# SPTSquidBoard.net
KiCad netlist of a schematic drawn in Altium Designer
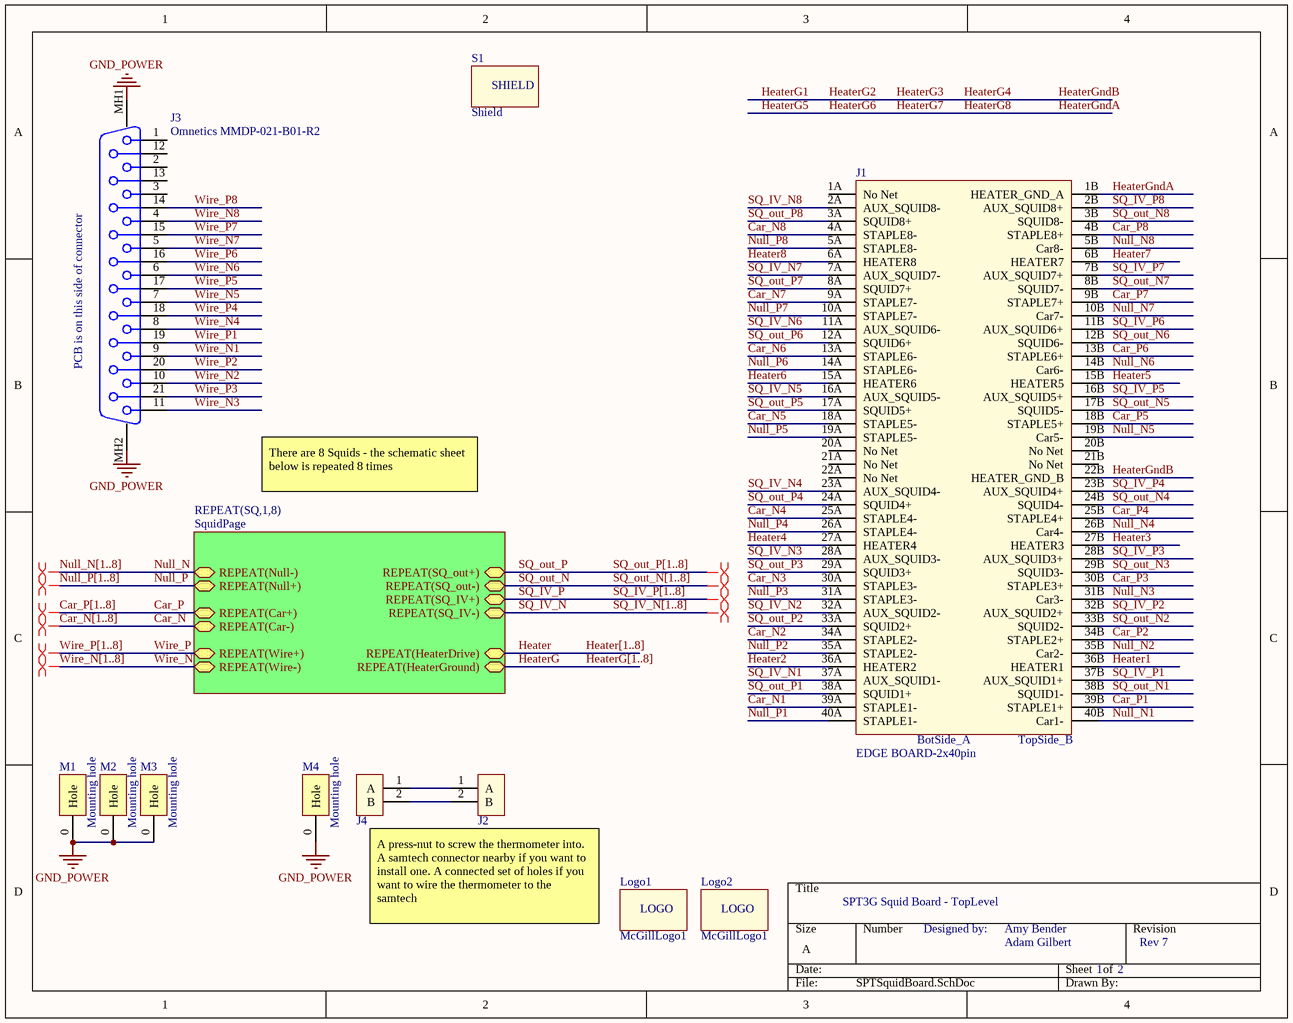
[diagram p0: SPTSquidBoard.SchDoc]

(export (version "E")
  (design (tool "Eeschema 10.0.6"))
  (components
    (comp (ref "J1")
      (value "EDGE BOARD-2x40pin")
      (description "Edge connector")
      (libsource (lib "SPT3G_LCBoard") (part "EDGE BOARD-2x40pin"))
    )
    (comp (ref "J2")
      (value "TempSenseWireConnection")
      (footprint "TempSenseWireCons")
      (libsource (lib "") (part "TempSenseCon_1"))
    )
    (comp (ref "J3")
      (value "Omnetics MMDP-021-B01-R2")
      (footprint "MMDP-021-B02-R2")
      (description "OmneticsMicroD21")
      (libsource (lib "SPT3G_LCBoard") (part "OmneticsMicroD21"))
    )
    (comp (ref "J4")
      (value "TempSenseWireConnection")
      (footprint "TempSenseWireCons")
      (libsource (lib "SPT3G_LCBoard") (part "TempSenseCon"))
    )
    (comp (ref "Logo1")
      (value "McGillLogo1")
      (footprint "McGillLogo1")
      (libsource (lib "SPT3G_LCBoard") (part "Logo"))
    )
    (comp (ref "Logo2")
      (value "McGillLogo1")
      (footprint "McGillLogo1")
      (libsource (lib "SPT3G_LCBoard") (part "Logo"))
    )
    (comp (ref "M1")
      (value "Mounting hole")
      (footprint "MountingHoleSquidBoard")
      (libsource (lib "SPT3G_LCBoard") (part "SquidBoardMountingHole"))
    )
    (comp (ref "M2")
      (value "Mounting hole")
      (footprint "MountingHoleSquidBoard")
      (libsource (lib "SPT3G_LCBoard") (part "SquidBoardMountingHole"))
    )
    (comp (ref "M3")
      (value "Mounting hole")
      (footprint "MountingHoleSquidBoard")
      (libsource (lib "SPT3G_LCBoard") (part "SquidBoardMountingHole"))
    )
    (comp (ref "M4")
      (value "Mounting hole")
      (footprint "MountingHoleSquidBoard")
      (libsource (lib "SPT3G_LCBoard") (part "SquidBoardMountingHole"))
    )
    (comp (ref "S1") (value "Shield") (footprint "Shield") (libsource (lib "SPT3G_LCBoard") (part "Shield")))
  )
  (nets
    (net (code "2") (name "/Car_N1") (class "Default")
      (node (ref "J1") (pin "39A") (pinfunction "STAPLE1-_39A") (pintype "passive"))
    )
    (net (code "3") (name "/Car_N2") (class "Default")
      (node (ref "J1") (pin "34A") (pinfunction "STAPLE2-_34A") (pintype "passive"))
    )
    (net (code "4") (name "/Car_N3") (class "Default")
      (node (ref "J1") (pin "30A") (pinfunction "STAPLE3-_30A") (pintype "passive"))
    )
    (net (code "5") (name "/Car_N4") (class "Default")
      (node (ref "J1") (pin "25A") (pinfunction "STAPLE4-_25A") (pintype "passive"))
    )
    (net (code "6") (name "/Car_N5") (class "Default")
      (node (ref "J1") (pin "18A") (pinfunction "STAPLE5-_18A") (pintype "passive"))
    )
    (net (code "7") (name "/Car_N6") (class "Default")
      (node (ref "J1") (pin "13A") (pinfunction "STAPLE6-_13A") (pintype "passive"))
    )
    (net (code "8") (name "/Car_N7") (class "Default")
      (node (ref "J1") (pin "9A") (pinfunction "STAPLE7-_9A") (pintype "passive"))
    )
    (net (code "9") (name "/Car_N8") (class "Default")
      (node (ref "J1") (pin "4A") (pinfunction "STAPLE8-_4A") (pintype "passive"))
    )
    (net (code "12") (name "/Car_P1") (class "Default")
      (node (ref "J1") (pin "39B") (pinfunction "STAPLE1+_39B") (pintype "passive"))
    )
    (net (code "13") (name "/Car_P2") (class "Default")
      (node (ref "J1") (pin "34B") (pinfunction "STAPLE2+_34B") (pintype "passive"))
    )
    (net (code "14") (name "/Car_P3") (class "Default")
      (node (ref "J1") (pin "30B") (pinfunction "STAPLE3+_30B") (pintype "passive"))
    )
    (net (code "15") (name "/Car_P4") (class "Default")
      (node (ref "J1") (pin "25B") (pinfunction "STAPLE4+_25B") (pintype "passive"))
    )
    (net (code "16") (name "/Car_P5") (class "Default")
      (node (ref "J1") (pin "18B") (pinfunction "STAPLE5+_18B") (pintype "passive"))
    )
    (net (code "17") (name "/Car_P6") (class "Default")
      (node (ref "J1") (pin "13B") (pinfunction "STAPLE6+_13B") (pintype "passive"))
    )
    (net (code "18") (name "/Car_P7") (class "Default")
      (node (ref "J1") (pin "9B") (pinfunction "STAPLE7+_9B") (pintype "passive"))
    )
    (net (code "19") (name "/Car_P8") (class "Default")
      (node (ref "J1") (pin "4B") (pinfunction "STAPLE8+_4B") (pintype "passive"))
    )
    (net (code "22") (name "/Heater1") (class "Default")
      (node (ref "J1") (pin "36B") (pinfunction "HEATER1_36B") (pintype "passive"))
    )
    (net (code "23") (name "/Heater2") (class "Default")
      (node (ref "J1") (pin "36A") (pinfunction "HEATER2_36A") (pintype "passive"))
    )
    (net (code "24") (name "/Heater3") (class "Default")
      (node (ref "J1") (pin "27B") (pinfunction "HEATER3_27B") (pintype "passive"))
    )
    (net (code "25") (name "/Heater4") (class "Default")
      (node (ref "J1") (pin "27A") (pinfunction "HEATER4_27A") (pintype "passive"))
    )
    (net (code "26") (name "/Heater5") (class "Default")
      (node (ref "J1") (pin "15B") (pinfunction "HEATER5_15B") (pintype "passive"))
    )
    (net (code "27") (name "/Heater6") (class "Default")
      (node (ref "J1") (pin "15A") (pinfunction "HEATER6_15A") (pintype "passive"))
    )
    (net (code "28") (name "/Heater7") (class "Default")
      (node (ref "J1") (pin "6B") (pinfunction "HEATER7_6B") (pintype "passive"))
    )
    (net (code "29") (name "/Heater8") (class "Default")
      (node (ref "J1") (pin "6A") (pinfunction "HEATER8_6A") (pintype "passive"))
    )
    (net (code "31") (name "/HeaterG4") (class "Default")
      (node (ref "J1") (pin "22B") (pinfunction "HEATER_GND_B_22B") (pintype "passive"))
    )
    (net (code "32") (name "/HeaterG8") (class "Default")
      (node (ref "J1") (pin "1B") (pinfunction "HEATER_GND_A_1B") (pintype "passive"))
    )
    (net (code "36") (name "/Null_N1") (class "Default")
      (node (ref "J1") (pin "40B") (pinfunction "Car1-_40B") (pintype "passive"))
    )
    (net (code "37") (name "/Null_N2") (class "Default")
      (node (ref "J1") (pin "35B") (pinfunction "Car2-_35B") (pintype "passive"))
    )
    (net (code "38") (name "/Null_N3") (class "Default")
      (node (ref "J1") (pin "31B") (pinfunction "Car3-_31B") (pintype "passive"))
    )
    (net (code "39") (name "/Null_N4") (class "Default")
      (node (ref "J1") (pin "26B") (pinfunction "Car4-_26B") (pintype "passive"))
    )
    (net (code "40") (name "/Null_N5") (class "Default")
      (node (ref "J1") (pin "19B") (pinfunction "Car5-_19B") (pintype "passive"))
    )
    (net (code "41") (name "/Null_N6") (class "Default")
      (node (ref "J1") (pin "14B") (pinfunction "Car6-_14B") (pintype "passive"))
    )
    (net (code "42") (name "/Null_N7") (class "Default")
      (node (ref "J1") (pin "10B") (pinfunction "Car7-_10B") (pintype "passive"))
    )
    (net (code "43") (name "/Null_N8") (class "Default")
      (node (ref "J1") (pin "5B") (pinfunction "Car8-_5B") (pintype "passive"))
    )
    (net (code "46") (name "/Null_P1") (class "Default")
      (node (ref "J1") (pin "40A") (pinfunction "STAPLE1-_40A") (pintype "passive"))
    )
    (net (code "47") (name "/Null_P2") (class "Default")
      (node (ref "J1") (pin "35A") (pinfunction "STAPLE2-_35A") (pintype "passive"))
    )
    (net (code "48") (name "/Null_P3") (class "Default")
      (node (ref "J1") (pin "31A") (pinfunction "STAPLE3-_31A") (pintype "passive"))
    )
    (net (code "49") (name "/Null_P4") (class "Default")
      (node (ref "J1") (pin "26A") (pinfunction "STAPLE4-_26A") (pintype "passive"))
    )
    (net (code "50") (name "/Null_P5") (class "Default")
      (node (ref "J1") (pin "19A") (pinfunction "STAPLE5-_19A") (pintype "passive"))
    )
    (net (code "51") (name "/Null_P6") (class "Default")
      (node (ref "J1") (pin "14A") (pinfunction "STAPLE6-_14A") (pintype "passive"))
    )
    (net (code "52") (name "/Null_P7") (class "Default")
      (node (ref "J1") (pin "10A") (pinfunction "STAPLE7-_10A") (pintype "passive"))
    )
    (net (code "53") (name "/Null_P8") (class "Default")
      (node (ref "J1") (pin "5A") (pinfunction "STAPLE8-_5A") (pintype "passive"))
    )
    (net (code "56") (name "/SQ_IV_N1") (class "Default")
      (node (ref "J1") (pin "37A") (pinfunction "AUX_SQUID1-_37A") (pintype "passive"))
    )
    (net (code "57") (name "/SQ_IV_N2") (class "Default")
      (node (ref "J1") (pin "32A") (pinfunction "AUX_SQUID2-_32A") (pintype "passive"))
    )
    (net (code "58") (name "/SQ_IV_N3") (class "Default")
      (node (ref "J1") (pin "28A") (pinfunction "AUX_SQUID3-_28A") (pintype "passive"))
    )
    (net (code "59") (name "/SQ_IV_N4") (class "Default")
      (node (ref "J1") (pin "23A") (pinfunction "AUX_SQUID4-_23A") (pintype "passive"))
    )
    (net (code "60") (name "/SQ_IV_N5") (class "Default")
      (node (ref "J1") (pin "16A") (pinfunction "AUX_SQUID5-_16A") (pintype "passive"))
    )
    (net (code "61") (name "/SQ_IV_N6") (class "Default")
      (node (ref "J1") (pin "11A") (pinfunction "AUX_SQUID6-_11A") (pintype "passive"))
    )
    (net (code "62") (name "/SQ_IV_N7") (class "Default")
      (node (ref "J1") (pin "7A") (pinfunction "AUX_SQUID7-_7A") (pintype "passive"))
    )
    (net (code "63") (name "/SQ_IV_N8") (class "Default")
      (node (ref "J1") (pin "2A") (pinfunction "AUX_SQUID8-_2A") (pintype "passive"))
    )
    (net (code "66") (name "/SQ_IV_P1") (class "Default")
      (node (ref "J1") (pin "37B") (pinfunction "AUX_SQUID1+_37B") (pintype "passive"))
    )
    (net (code "67") (name "/SQ_IV_P2") (class "Default")
      (node (ref "J1") (pin "32B") (pinfunction "AUX_SQUID2+_32B") (pintype "passive"))
    )
    (net (code "68") (name "/SQ_IV_P3") (class "Default")
      (node (ref "J1") (pin "28B") (pinfunction "AUX_SQUID3+_28B") (pintype "passive"))
    )
    (net (code "69") (name "/SQ_IV_P4") (class "Default")
      (node (ref "J1") (pin "23B") (pinfunction "AUX_SQUID4+_23B") (pintype "passive"))
    )
    (net (code "70") (name "/SQ_IV_P5") (class "Default")
      (node (ref "J1") (pin "16B") (pinfunction "AUX_SQUID5+_16B") (pintype "passive"))
    )
    (net (code "71") (name "/SQ_IV_P6") (class "Default")
      (node (ref "J1") (pin "11B") (pinfunction "AUX_SQUID6+_11B") (pintype "passive"))
    )
    (net (code "72") (name "/SQ_IV_P7") (class "Default")
      (node (ref "J1") (pin "7B") (pinfunction "AUX_SQUID7+_7B") (pintype "passive"))
    )
    (net (code "73") (name "/SQ_IV_P8") (class "Default")
      (node (ref "J1") (pin "2B") (pinfunction "AUX_SQUID8+_2B") (pintype "passive"))
    )
    (net (code "76") (name "/SQ_out_N1") (class "Default")
      (node (ref "J1") (pin "38B") (pinfunction "SQUID1-_38B") (pintype "passive"))
    )
    (net (code "77") (name "/SQ_out_N2") (class "Default")
      (node (ref "J1") (pin "33B") (pinfunction "SQUID2-_33B") (pintype "passive"))
    )
    (net (code "78") (name "/SQ_out_N3") (class "Default")
      (node (ref "J1") (pin "29B") (pinfunction "SQUID3-_29B") (pintype "passive"))
    )
    (net (code "79") (name "/SQ_out_N4") (class "Default")
      (node (ref "J1") (pin "24B") (pinfunction "SQUID4-_24B") (pintype "passive"))
    )
    (net (code "80") (name "/SQ_out_N5") (class "Default")
      (node (ref "J1") (pin "17B") (pinfunction "SQUID5-_17B") (pintype "passive"))
    )
    (net (code "81") (name "/SQ_out_N6") (class "Default")
      (node (ref "J1") (pin "12B") (pinfunction "SQUID6-_12B") (pintype "passive"))
    )
    (net (code "82") (name "/SQ_out_N7") (class "Default")
      (node (ref "J1") (pin "8B") (pinfunction "SQUID7-_8B") (pintype "passive"))
    )
    (net (code "83") (name "/SQ_out_N8") (class "Default")
      (node (ref "J1") (pin "3B") (pinfunction "SQUID8-_3B") (pintype "passive"))
    )
    (net (code "86") (name "/SQ_out_P1") (class "Default")
      (node (ref "J1") (pin "38A") (pinfunction "SQUID1+_38A") (pintype "passive"))
    )
    (net (code "87") (name "/SQ_out_P2") (class "Default")
      (node (ref "J1") (pin "33A") (pinfunction "SQUID2+_33A") (pintype "passive"))
    )
    (net (code "88") (name "/SQ_out_P3") (class "Default")
      (node (ref "J1") (pin "29A") (pinfunction "SQUID3+_29A") (pintype "passive"))
    )
    (net (code "89") (name "/SQ_out_P4") (class "Default")
      (node (ref "J1") (pin "24A") (pinfunction "SQUID4+_24A") (pintype "passive"))
    )
    (net (code "90") (name "/SQ_out_P5") (class "Default")
      (node (ref "J1") (pin "17A") (pinfunction "SQUID5+_17A") (pintype "passive"))
    )
    (net (code "91") (name "/SQ_out_P6") (class "Default")
      (node (ref "J1") (pin "12A") (pinfunction "SQUID6+_12A") (pintype "passive"))
    )
    (net (code "92") (name "/SQ_out_P7") (class "Default")
      (node (ref "J1") (pin "8A") (pinfunction "SQUID7+_8A") (pintype "passive"))
    )
    (net (code "93") (name "/SQ_out_P8") (class "Default")
      (node (ref "J1") (pin "3A") (pinfunction "SQUID8+_3A") (pintype "passive"))
    )
    (net (code "96") (name "/Wire_N1") (class "Default")
      (node (ref "J3") (pin "9") (pinfunction "9_9") (pintype "passive"))
    )
    (net (code "97") (name "/Wire_N2") (class "Default")
      (node (ref "J3") (pin "10") (pinfunction "10_10") (pintype "passive"))
    )
    (net (code "98") (name "/Wire_N3") (class "Default")
      (node (ref "J3") (pin "11") (pinfunction "11_11") (pintype "passive"))
    )
    (net (code "99") (name "/Wire_N4") (class "Default")
      (node (ref "J3") (pin "8") (pinfunction "8_8") (pintype "passive"))
    )
    (net (code "100") (name "/Wire_N5") (class "Default")
      (node (ref "J3") (pin "7") (pinfunction "7_7") (pintype "passive"))
    )
    (net (code "101") (name "/Wire_N6") (class "Default")
      (node (ref "J3") (pin "6") (pinfunction "6_6") (pintype "passive"))
    )
    (net (code "102") (name "/Wire_N7") (class "Default")
      (node (ref "J3") (pin "5") (pinfunction "5_5") (pintype "passive"))
    )
    (net (code "103") (name "/Wire_N8") (class "Default")
      (node (ref "J3") (pin "4") (pinfunction "4_4") (pintype "passive"))
    )
    (net (code "106") (name "/Wire_P1") (class "Default")
      (node (ref "J3") (pin "19") (pinfunction "19_19") (pintype "passive"))
    )
    (net (code "107") (name "/Wire_P2") (class "Default")
      (node (ref "J3") (pin "20") (pinfunction "20_20") (pintype "passive"))
    )
    (net (code "108") (name "/Wire_P3") (class "Default")
      (node (ref "J3") (pin "21") (pinfunction "21_21") (pintype "passive"))
    )
    (net (code "109") (name "/Wire_P4") (class "Default")
      (node (ref "J3") (pin "18") (pinfunction "18_18") (pintype "passive"))
    )
    (net (code "110") (name "/Wire_P5") (class "Default")
      (node (ref "J3") (pin "17") (pinfunction "17_17") (pintype "passive"))
    )
    (net (code "111") (name "/Wire_P6") (class "Default")
      (node (ref "J3") (pin "16") (pinfunction "16_16") (pintype "passive"))
    )
    (net (code "112") (name "/Wire_P7") (class "Default")
      (node (ref "J3") (pin "15") (pinfunction "15_15") (pintype "passive"))
    )
    (net (code "113") (name "/Wire_P8") (class "Default")
      (node (ref "J3") (pin "14") (pinfunction "14_14") (pintype "passive"))
    )
    (net (code "115") (name "GND_POWER") (class "Default")
      (node (ref "J3") (pin "MH1") (pinfunction "MH1_MH1") (pintype "passive"))
      (node (ref "J3") (pin "MH2") (pinfunction "MH2_MH2") (pintype "passive"))
      (node (ref "M1") (pin "0") (pinfunction "Hole_0") (pintype "passive"))
      (node (ref "M2") (pin "0") (pinfunction "Hole_0") (pintype "passive"))
      (node (ref "M3") (pin "0") (pinfunction "Hole_0") (pintype "passive"))
      (node (ref "M4") (pin "0") (pinfunction "Hole_0") (pintype "passive"))
    )
    (net (code "116") (name "Net-(J2-A)") (class "Default")
      (node (ref "J2") (pin "1") (pinfunction "A_1") (pintype "passive"))
      (node (ref "J4") (pin "1") (pinfunction "A_1") (pintype "passive"))
    )
    (net (code "117") (name "Net-(J2-B)") (class "Default")
      (node (ref "J2") (pin "2") (pinfunction "B_2") (pintype "passive"))
      (node (ref "J4") (pin "2") (pinfunction "B_2") (pintype "passive"))
    )
    (net (code "118") (name "unconnected-(J1-No_Net-Pad1A)") (class "Default")
      (node (ref "J1") (pin "1A") (pinfunction "No_Net_1A") (pintype "passive"))
    )
    (net (code "119") (name "unconnected-(J1-No_Net-Pad20A)") (class "Default")
      (node (ref "J1") (pin "20A") (pinfunction "No_Net_20A") (pintype "passive"))
    )
    (net (code "120") (name "unconnected-(J1-No_Net-Pad20B)") (class "Default")
      (node (ref "J1") (pin "20B") (pinfunction "No_Net_20B") (pintype "passive"))
    )
    (net (code "121") (name "unconnected-(J1-No_Net-Pad21A)") (class "Default")
      (node (ref "J1") (pin "21A") (pinfunction "No_Net_21A") (pintype "passive"))
    )
    (net (code "122") (name "unconnected-(J1-No_Net-Pad21B)") (class "Default")
      (node (ref "J1") (pin "21B") (pinfunction "No_Net_21B") (pintype "passive"))
    )
    (net (code "123") (name "unconnected-(J1-No_Net-Pad22A)") (class "Default")
      (node (ref "J1") (pin "22A") (pinfunction "No_Net_22A") (pintype "passive"))
    )
    (net (code "124") (name "unconnected-(J3-Pad1)") (class "Default")
      (node (ref "J3") (pin "1") (pinfunction "1_1") (pintype "passive"))
    )
    (net (code "125") (name "unconnected-(J3-Pad2)") (class "Default")
      (node (ref "J3") (pin "2") (pinfunction "2_2") (pintype "passive"))
    )
    (net (code "126") (name "unconnected-(J3-Pad3)") (class "Default")
      (node (ref "J3") (pin "3") (pinfunction "3_3") (pintype "passive"))
    )
    (net (code "127") (name "unconnected-(J3-Pad12)") (class "Default")
      (node (ref "J3") (pin "12") (pinfunction "12_12") (pintype "passive"))
    )
    (net (code "128") (name "unconnected-(J3-Pad13)") (class "Default")
      (node (ref "J3") (pin "13") (pinfunction "13_13") (pintype "passive"))
    )
  )
)
